# SFPGA_power.net
KiCad netlist of a schematic drawn in Altium Designer
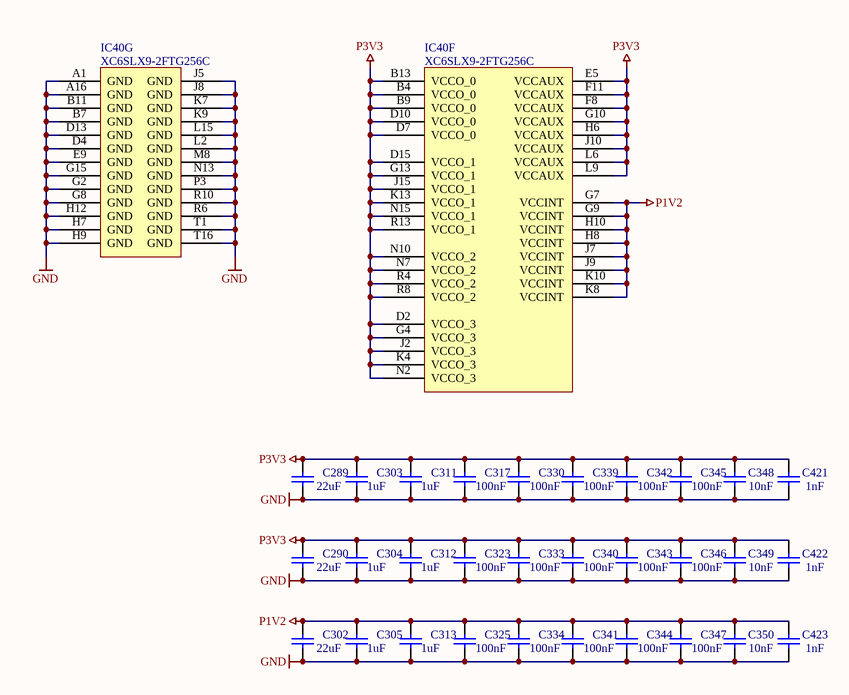
[diagram p0: SFPGA_power.SchDoc]

(export (version "E")
  (design (tool "Eeschema 10.0.6"))
  (components
    (comp (ref "C289")
      (value "22uF")
      (footprint "CAPC3216X180N")
      (description "Non-polarised capacitor")
      (fields
        (field (name "PART NUMBER") "CC1206_22UF_10V_10%_X7R")
        (field (name "VOLTAGE") "10V")
        (field (name "AUTHOR") "CERN DEM JLC")
      )
      (libsource (lib "Capacitors") (part "Capacitor - non polarized"))
    )
    (comp (ref "C290")
      (value "22uF")
      (footprint "CAPC3216X180N")
      (description "Non-polarised capacitor")
      (fields
        (field (name "PART NUMBER") "CC1206_22UF_10V_10%_X7R")
        (field (name "VOLTAGE") "10V")
        (field (name "AUTHOR") "CERN DEM JLC")
      )
      (libsource (lib "Capacitors") (part "Capacitor - non polarized"))
    )
    (comp (ref "C302")
      (value "22uF")
      (footprint "CAPC3216X180N")
      (description "Non-polarised capacitor")
      (fields
        (field (name "PART NUMBER") "CC1206_22UF_10V_10%_X7R")
        (field (name "VOLTAGE") "10V")
        (field (name "AUTHOR") "CERN DEM JLC")
      )
      (libsource (lib "Capacitors") (part "Capacitor - non polarized"))
    )
    (comp (ref "C303")
      (value "1uF")
      (footprint "CAPC1608X87N")
      (description "Non-polarised capacitor")
      (fields
        (field (name "PART NUMBER") "CC0603_1UF_16V_10%_X7R")
        (field (name "VOLTAGE") "16V")
        (field (name "AUTHOR") "CERN DEM JLC")
      )
      (libsource (lib "Capacitors") (part "Capacitor - non polarized"))
    )
    (comp (ref "C304")
      (value "1uF")
      (footprint "CAPC1608X87N")
      (description "Non-polarised capacitor")
      (fields
        (field (name "PART NUMBER") "CC0603_1UF_16V_10%_X7R")
        (field (name "VOLTAGE") "16V")
        (field (name "AUTHOR") "CERN DEM JLC")
      )
      (libsource (lib "Capacitors") (part "Capacitor - non polarized"))
    )
    (comp (ref "C305")
      (value "1uF")
      (footprint "CAPC1608X87N")
      (description "Non-polarised capacitor")
      (fields
        (field (name "PART NUMBER") "CC0603_1UF_16V_10%_X7R")
        (field (name "VOLTAGE") "16V")
        (field (name "AUTHOR") "CERN DEM JLC")
      )
      (libsource (lib "Capacitors") (part "Capacitor - non polarized"))
    )
    (comp (ref "C311")
      (value "1uF")
      (footprint "CAPC1608X87N")
      (description "Non-polarised capacitor")
      (fields
        (field (name "PART NUMBER") "CC0603_1UF_16V_10%_X7R")
        (field (name "VOLTAGE") "16V")
        (field (name "AUTHOR") "CERN DEM JLC")
      )
      (libsource (lib "Capacitors") (part "Capacitor - non polarized"))
    )
    (comp (ref "C312")
      (value "1uF")
      (footprint "CAPC1608X87N")
      (description "Non-polarised capacitor")
      (fields
        (field (name "PART NUMBER") "CC0603_1UF_16V_10%_X7R")
        (field (name "VOLTAGE") "16V")
        (field (name "AUTHOR") "CERN DEM JLC")
      )
      (libsource (lib "Capacitors") (part "Capacitor - non polarized"))
    )
    (comp (ref "C313")
      (value "1uF")
      (footprint "CAPC1608X87N")
      (description "Non-polarised capacitor")
      (fields
        (field (name "PART NUMBER") "CC0603_1UF_16V_10%_X7R")
        (field (name "VOLTAGE") "16V")
        (field (name "AUTHOR") "CERN DEM JLC")
      )
      (libsource (lib "Capacitors") (part "Capacitor - non polarized"))
    )
    (comp (ref "C317")
      (value "100nF")
      (footprint "CAPC1005X55N")
      (description "Non-polarised capacitor")
      (fields
        (field (name "PART NUMBER") "CC0402_100NF_16V_10%_X7R")
        (field (name "VOLTAGE") "16V")
        (field (name "AUTHOR") "CERN DEM JLC")
      )
      (libsource (lib "Capacitors") (part "Capacitor - non polarized"))
    )
    (comp (ref "C323")
      (value "100nF")
      (footprint "CAPC1005X55N")
      (description "Non-polarised capacitor")
      (fields
        (field (name "PART NUMBER") "CC0402_100NF_16V_10%_X7R")
        (field (name "VOLTAGE") "16V")
        (field (name "AUTHOR") "CERN DEM JLC")
      )
      (libsource (lib "Capacitors") (part "Capacitor - non polarized"))
    )
    (comp (ref "C325")
      (value "100nF")
      (footprint "CAPC1005X55N")
      (description "Non-polarised capacitor")
      (fields
        (field (name "PART NUMBER") "CC0402_100NF_16V_10%_X7R")
        (field (name "VOLTAGE") "16V")
        (field (name "AUTHOR") "CERN DEM JLC")
      )
      (libsource (lib "Capacitors") (part "Capacitor - non polarized"))
    )
    (comp (ref "C330")
      (value "100nF")
      (footprint "CAPC1005X55N")
      (description "Non-polarised capacitor")
      (fields
        (field (name "PART NUMBER") "CC0402_100NF_16V_10%_X7R")
        (field (name "VOLTAGE") "16V")
        (field (name "AUTHOR") "CERN DEM JLC")
      )
      (libsource (lib "Capacitors") (part "Capacitor - non polarized"))
    )
    (comp (ref "C333")
      (value "100nF")
      (footprint "CAPC1005X55N")
      (description "Non-polarised capacitor")
      (fields
        (field (name "PART NUMBER") "CC0402_100NF_16V_10%_X7R")
        (field (name "VOLTAGE") "16V")
        (field (name "AUTHOR") "CERN DEM JLC")
      )
      (libsource (lib "Capacitors") (part "Capacitor - non polarized"))
    )
    (comp (ref "C334")
      (value "100nF")
      (footprint "CAPC1005X55N")
      (description "Non-polarised capacitor")
      (fields
        (field (name "PART NUMBER") "CC0402_100NF_16V_10%_X7R")
        (field (name "VOLTAGE") "16V")
        (field (name "AUTHOR") "CERN DEM JLC")
      )
      (libsource (lib "Capacitors") (part "Capacitor - non polarized"))
    )
    (comp (ref "C339")
      (value "100nF")
      (footprint "CAPC1005X55N")
      (description "Non-polarised capacitor")
      (fields
        (field (name "PART NUMBER") "CC0402_100NF_16V_10%_X7R")
        (field (name "VOLTAGE") "16V")
        (field (name "AUTHOR") "CERN DEM JLC")
      )
      (libsource (lib "Capacitors") (part "Capacitor - non polarized"))
    )
    (comp (ref "C340")
      (value "100nF")
      (footprint "CAPC1005X55N")
      (description "Non-polarised capacitor")
      (fields
        (field (name "PART NUMBER") "CC0402_100NF_16V_10%_X7R")
        (field (name "VOLTAGE") "16V")
        (field (name "AUTHOR") "CERN DEM JLC")
      )
      (libsource (lib "Capacitors") (part "Capacitor - non polarized"))
    )
    (comp (ref "C341")
      (value "100nF")
      (footprint "CAPC1005X55N")
      (description "Non-polarised capacitor")
      (fields
        (field (name "PART NUMBER") "CC0402_100NF_16V_10%_X7R")
        (field (name "VOLTAGE") "16V")
        (field (name "AUTHOR") "CERN DEM JLC")
      )
      (libsource (lib "Capacitors") (part "Capacitor - non polarized"))
    )
    (comp (ref "C342")
      (value "100nF")
      (footprint "CAPC1005X55N")
      (description "Non-polarised capacitor")
      (fields
        (field (name "PART NUMBER") "CC0402_100NF_16V_10%_X7R")
        (field (name "VOLTAGE") "16V")
        (field (name "AUTHOR") "CERN DEM JLC")
      )
      (libsource (lib "Capacitors") (part "Capacitor - non polarized"))
    )
    (comp (ref "C343")
      (value "100nF")
      (footprint "CAPC1005X55N")
      (description "Non-polarised capacitor")
      (fields
        (field (name "PART NUMBER") "CC0402_100NF_16V_10%_X7R")
        (field (name "VOLTAGE") "16V")
        (field (name "AUTHOR") "CERN DEM JLC")
      )
      (libsource (lib "Capacitors") (part "Capacitor - non polarized"))
    )
    (comp (ref "C344")
      (value "100nF")
      (footprint "CAPC1005X55N")
      (description "Non-polarised capacitor")
      (fields
        (field (name "PART NUMBER") "CC0402_100NF_16V_10%_X7R")
        (field (name "VOLTAGE") "16V")
        (field (name "AUTHOR") "CERN DEM JLC")
      )
      (libsource (lib "Capacitors") (part "Capacitor - non polarized"))
    )
    (comp (ref "C345")
      (value "100nF")
      (footprint "CAPC1005X55N")
      (description "Non-polarised capacitor")
      (fields
        (field (name "PART NUMBER") "CC0402_100NF_16V_10%_X7R")
        (field (name "VOLTAGE") "16V")
        (field (name "AUTHOR") "CERN DEM JLC")
      )
      (libsource (lib "Capacitors") (part "Capacitor - non polarized"))
    )
    (comp (ref "C346")
      (value "100nF")
      (footprint "CAPC1005X55N")
      (description "Non-polarised capacitor")
      (fields
        (field (name "PART NUMBER") "CC0402_100NF_16V_10%_X7R")
        (field (name "VOLTAGE") "16V")
        (field (name "AUTHOR") "CERN DEM JLC")
      )
      (libsource (lib "Capacitors") (part "Capacitor - non polarized"))
    )
    (comp (ref "C347")
      (value "100nF")
      (footprint "CAPC1005X55N")
      (description "Non-polarised capacitor")
      (fields
        (field (name "PART NUMBER") "CC0402_100NF_16V_10%_X7R")
        (field (name "VOLTAGE") "16V")
        (field (name "AUTHOR") "CERN DEM JLC")
      )
      (libsource (lib "Capacitors") (part "Capacitor - non polarized"))
    )
    (comp (ref "C348")
      (value "10nF")
      (footprint "CAPC1608X87N")
      (description "Non-polarised capacitor")
      (fields
        (field (name "PART NUMBER") "CC0603_10NF_50V_10%_X7R")
        (field (name "VOLTAGE") "50V")
        (field (name "AUTHOR") "CERN DEM JLC")
      )
      (libsource (lib "Capacitors") (part "Capacitor - non polarized"))
    )
    (comp (ref "C349")
      (value "10nF")
      (footprint "CAPC1608X87N")
      (description "Non-polarised capacitor")
      (fields
        (field (name "PART NUMBER") "CC0603_10NF_50V_10%_X7R")
        (field (name "VOLTAGE") "50V")
        (field (name "AUTHOR") "CERN DEM JLC")
      )
      (libsource (lib "Capacitors") (part "Capacitor - non polarized"))
    )
    (comp (ref "C350")
      (value "10nF")
      (footprint "CAPC1608X87N")
      (description "Non-polarised capacitor")
      (fields
        (field (name "PART NUMBER") "CC0603_10NF_50V_10%_X7R")
        (field (name "VOLTAGE") "50V")
        (field (name "AUTHOR") "CERN DEM JLC")
      )
      (libsource (lib "Capacitors") (part "Capacitor - non polarized"))
    )
    (comp (ref "C421")
      (value "1nF")
      (footprint "CAPC1005X55N")
      (description "Non-polarised capacitor")
      (fields
        (field (name "PART NUMBER") "CC0402_1NF_50V_10%_X7R")
        (field (name "VOLTAGE") "50V")
        (field (name "AUTHOR") "CERN DEM JLC")
      )
      (libsource (lib "Capacitors") (part "Capacitor - non polarized"))
    )
    (comp (ref "C422")
      (value "1nF")
      (footprint "CAPC1005X55N")
      (description "Non-polarised capacitor")
      (fields
        (field (name "PART NUMBER") "CC0402_1NF_50V_10%_X7R")
        (field (name "VOLTAGE") "50V")
        (field (name "AUTHOR") "CERN DEM JLC")
      )
      (libsource (lib "Capacitors") (part "Capacitor - non polarized"))
    )
    (comp (ref "C423")
      (value "1nF")
      (footprint "CAPC1005X55N")
      (description "Non-polarised capacitor")
      (fields
        (field (name "PART NUMBER") "CC0402_1NF_50V_10%_X7R")
        (field (name "VOLTAGE") "50V")
        (field (name "AUTHOR") "CERN DEM JLC")
      )
      (libsource (lib "Capacitors") (part "Capacitor - non polarized"))
    )
    (comp (ref "IC40")
      (value "XC6SLX9-2FTG256C")
      (footprint "BGA256C100P16X16_1700X1700X155")
      (fields (field (name "MANUFACTURER") "XILINX") (field (name "AUTHOR") "CERN DEM JLC"))
      (libsource (lib "ICs And Semiconductors") (part "XC6SLX9-2FTG256C"))
    )
  )
  (nets
    (net (code "1") (name "GND") (class "Default")
      (node (ref "C289") (pin "1") (pinfunction "1_1") (pintype "passive"))
      (node (ref "C290") (pin "1") (pinfunction "1_1") (pintype "passive"))
      (node (ref "C302") (pin "1") (pinfunction "1_1") (pintype "passive"))
      (node (ref "C303") (pin "1") (pinfunction "1_1") (pintype "passive"))
      (node (ref "C304") (pin "1") (pinfunction "1_1") (pintype "passive"))
      (node (ref "C305") (pin "1") (pinfunction "1_1") (pintype "passive"))
      (node (ref "C311") (pin "1") (pinfunction "1_1") (pintype "passive"))
      (node (ref "C312") (pin "1") (pinfunction "1_1") (pintype "passive"))
      (node (ref "C313") (pin "1") (pinfunction "1_1") (pintype "passive"))
      (node (ref "C317") (pin "1") (pinfunction "1_1") (pintype "passive"))
      (node (ref "C323") (pin "1") (pinfunction "1_1") (pintype "passive"))
      (node (ref "C325") (pin "1") (pinfunction "1_1") (pintype "passive"))
      (node (ref "C330") (pin "1") (pinfunction "1_1") (pintype "passive"))
      (node (ref "C333") (pin "1") (pinfunction "1_1") (pintype "passive"))
      (node (ref "C334") (pin "1") (pinfunction "1_1") (pintype "passive"))
      (node (ref "C339") (pin "1") (pinfunction "1_1") (pintype "passive"))
      (node (ref "C340") (pin "1") (pinfunction "1_1") (pintype "passive"))
      (node (ref "C341") (pin "1") (pinfunction "1_1") (pintype "passive"))
      (node (ref "C342") (pin "1") (pinfunction "1_1") (pintype "passive"))
      (node (ref "C343") (pin "1") (pinfunction "1_1") (pintype "passive"))
      (node (ref "C344") (pin "1") (pinfunction "1_1") (pintype "passive"))
      (node (ref "C345") (pin "1") (pinfunction "1_1") (pintype "passive"))
      (node (ref "C346") (pin "1") (pinfunction "1_1") (pintype "passive"))
      (node (ref "C347") (pin "1") (pinfunction "1_1") (pintype "passive"))
      (node (ref "C348") (pin "1") (pinfunction "1_1") (pintype "passive"))
      (node (ref "C349") (pin "1") (pinfunction "1_1") (pintype "passive"))
      (node (ref "C350") (pin "1") (pinfunction "1_1") (pintype "passive"))
      (node (ref "C421") (pin "1") (pinfunction "1_1") (pintype "passive"))
      (node (ref "C422") (pin "1") (pinfunction "1_1") (pintype "passive"))
      (node (ref "C423") (pin "1") (pinfunction "1_1") (pintype "passive"))
      (node (ref "IC40") (pin "A1") (pinfunction "GND_A1") (pintype "power_in"))
      (node (ref "IC40") (pin "A16") (pinfunction "GND_A16") (pintype "power_in"))
      (node (ref "IC40") (pin "B11") (pinfunction "GND_B11") (pintype "power_in"))
      (node (ref "IC40") (pin "B7") (pinfunction "GND_B7") (pintype "power_in"))
      (node (ref "IC40") (pin "D13") (pinfunction "GND_D13") (pintype "power_in"))
      (node (ref "IC40") (pin "D4") (pinfunction "GND_D4") (pintype "power_in"))
      (node (ref "IC40") (pin "E9") (pinfunction "GND_E9") (pintype "power_in"))
      (node (ref "IC40") (pin "G15") (pinfunction "GND_G15") (pintype "power_in"))
      (node (ref "IC40") (pin "G2") (pinfunction "GND_G2") (pintype "power_in"))
      (node (ref "IC40") (pin "G8") (pinfunction "GND_G8") (pintype "power_in"))
      (node (ref "IC40") (pin "H12") (pinfunction "GND_H12") (pintype "power_in"))
      (node (ref "IC40") (pin "H7") (pinfunction "GND_H7") (pintype "power_in"))
      (node (ref "IC40") (pin "H9") (pinfunction "GND_H9") (pintype "power_in"))
      (node (ref "IC40") (pin "J5") (pinfunction "GND_J5") (pintype "power_in"))
      (node (ref "IC40") (pin "J8") (pinfunction "GND_J8") (pintype "power_in"))
      (node (ref "IC40") (pin "K7") (pinfunction "GND_K7") (pintype "power_in"))
      (node (ref "IC40") (pin "K9") (pinfunction "GND_K9") (pintype "power_in"))
      (node (ref "IC40") (pin "L15") (pinfunction "GND_L15") (pintype "power_in"))
      (node (ref "IC40") (pin "L2") (pinfunction "GND_L2") (pintype "power_in"))
      (node (ref "IC40") (pin "M8") (pinfunction "GND_M8") (pintype "power_in"))
      (node (ref "IC40") (pin "N13") (pinfunction "GND_N13") (pintype "power_in"))
      (node (ref "IC40") (pin "P3") (pinfunction "GND_P3") (pintype "power_in"))
      (node (ref "IC40") (pin "R10") (pinfunction "GND_R10") (pintype "power_in"))
      (node (ref "IC40") (pin "R6") (pinfunction "GND_R6") (pintype "power_in"))
      (node (ref "IC40") (pin "T1") (pinfunction "GND_T1") (pintype "power_in"))
      (node (ref "IC40") (pin "T16") (pinfunction "GND_T16") (pintype "power_in"))
    )
    (net (code "2") (name "P1V2") (class "Default")
      (node (ref "C302") (pin "2") (pinfunction "2_2") (pintype "passive"))
      (node (ref "C305") (pin "2") (pinfunction "2_2") (pintype "passive"))
      (node (ref "C313") (pin "2") (pinfunction "2_2") (pintype "passive"))
      (node (ref "C325") (pin "2") (pinfunction "2_2") (pintype "passive"))
      (node (ref "C334") (pin "2") (pinfunction "2_2") (pintype "passive"))
      (node (ref "C341") (pin "2") (pinfunction "2_2") (pintype "passive"))
      (node (ref "C344") (pin "2") (pinfunction "2_2") (pintype "passive"))
      (node (ref "C347") (pin "2") (pinfunction "2_2") (pintype "passive"))
      (node (ref "C350") (pin "2") (pinfunction "2_2") (pintype "passive"))
      (node (ref "C423") (pin "2") (pinfunction "2_2") (pintype "passive"))
      (node (ref "IC40") (pin "G7") (pinfunction "VCCINT_G7") (pintype "power_in"))
      (node (ref "IC40") (pin "G9") (pinfunction "VCCINT_G9") (pintype "power_in"))
      (node (ref "IC40") (pin "H10") (pinfunction "VCCINT_H10") (pintype "power_in"))
      (node (ref "IC40") (pin "H8") (pinfunction "VCCINT_H8") (pintype "power_in"))
      (node (ref "IC40") (pin "J7") (pinfunction "VCCINT_J7") (pintype "power_in"))
      (node (ref "IC40") (pin "J9") (pinfunction "VCCINT_J9") (pintype "power_in"))
      (node (ref "IC40") (pin "K10") (pinfunction "VCCINT_K10") (pintype "power_in"))
      (node (ref "IC40") (pin "K8") (pinfunction "VCCINT_K8") (pintype "power_in"))
    )
    (net (code "3") (name "P3V3") (class "Default")
      (node (ref "C289") (pin "2") (pinfunction "2_2") (pintype "passive"))
      (node (ref "C290") (pin "2") (pinfunction "2_2") (pintype "passive"))
      (node (ref "C303") (pin "2") (pinfunction "2_2") (pintype "passive"))
      (node (ref "C304") (pin "2") (pinfunction "2_2") (pintype "passive"))
      (node (ref "C311") (pin "2") (pinfunction "2_2") (pintype "passive"))
      (node (ref "C312") (pin "2") (pinfunction "2_2") (pintype "passive"))
      (node (ref "C317") (pin "2") (pinfunction "2_2") (pintype "passive"))
      (node (ref "C323") (pin "2") (pinfunction "2_2") (pintype "passive"))
      (node (ref "C330") (pin "2") (pinfunction "2_2") (pintype "passive"))
      (node (ref "C333") (pin "2") (pinfunction "2_2") (pintype "passive"))
      (node (ref "C339") (pin "2") (pinfunction "2_2") (pintype "passive"))
      (node (ref "C340") (pin "2") (pinfunction "2_2") (pintype "passive"))
      (node (ref "C342") (pin "2") (pinfunction "2_2") (pintype "passive"))
      (node (ref "C343") (pin "2") (pinfunction "2_2") (pintype "passive"))
      (node (ref "C345") (pin "2") (pinfunction "2_2") (pintype "passive"))
      (node (ref "C346") (pin "2") (pinfunction "2_2") (pintype "passive"))
      (node (ref "C348") (pin "2") (pinfunction "2_2") (pintype "passive"))
      (node (ref "C349") (pin "2") (pinfunction "2_2") (pintype "passive"))
      (node (ref "C421") (pin "2") (pinfunction "2_2") (pintype "passive"))
      (node (ref "C422") (pin "2") (pinfunction "2_2") (pintype "passive"))
      (node (ref "IC40") (pin "B13") (pinfunction "VCCO_0_B13") (pintype "power_in"))
      (node (ref "IC40") (pin "B4") (pinfunction "VCCO_0_B4") (pintype "power_in"))
      (node (ref "IC40") (pin "B9") (pinfunction "VCCO_0_B9") (pintype "power_in"))
      (node (ref "IC40") (pin "D10") (pinfunction "VCCO_0_D10") (pintype "power_in"))
      (node (ref "IC40") (pin "D15") (pinfunction "VCCO_1_D15") (pintype "power_in"))
      (node (ref "IC40") (pin "D2") (pinfunction "VCCO_3_D2") (pintype "power_in"))
      (node (ref "IC40") (pin "D7") (pinfunction "VCCO_0_D7") (pintype "power_in"))
      (node (ref "IC40") (pin "E5") (pinfunction "VCCAUX_E5") (pintype "power_in"))
      (node (ref "IC40") (pin "F11") (pinfunction "VCCAUX_F11") (pintype "power_in"))
      (node (ref "IC40") (pin "F8") (pinfunction "VCCAUX_F8") (pintype "power_in"))
      (node (ref "IC40") (pin "G10") (pinfunction "VCCAUX_G10") (pintype "power_in"))
      (node (ref "IC40") (pin "G13") (pinfunction "VCCO_1_G13") (pintype "power_in"))
      (node (ref "IC40") (pin "G4") (pinfunction "VCCO_3_G4") (pintype "power_in"))
      (node (ref "IC40") (pin "H6") (pinfunction "VCCAUX_H6") (pintype "power_in"))
      (node (ref "IC40") (pin "J10") (pinfunction "VCCAUX_J10") (pintype "power_in"))
      (node (ref "IC40") (pin "J15") (pinfunction "VCCO_1_J15") (pintype "power_in"))
      (node (ref "IC40") (pin "J2") (pinfunction "VCCO_3_J2") (pintype "power_in"))
      (node (ref "IC40") (pin "K13") (pinfunction "VCCO_1_K13") (pintype "power_in"))
      (node (ref "IC40") (pin "K4") (pinfunction "VCCO_3_K4") (pintype "power_in"))
      (node (ref "IC40") (pin "L6") (pinfunction "VCCAUX_L6") (pintype "power_in"))
      (node (ref "IC40") (pin "L9") (pinfunction "VCCAUX_L9") (pintype "power_in"))
      (node (ref "IC40") (pin "N10") (pinfunction "VCCO_2_N10") (pintype "power_in"))
      (node (ref "IC40") (pin "N15") (pinfunction "VCCO_1_N15") (pintype "power_in"))
      (node (ref "IC40") (pin "N2") (pinfunction "VCCO_3_N2") (pintype "power_in"))
      (node (ref "IC40") (pin "N7") (pinfunction "VCCO_2_N7") (pintype "power_in"))
      (node (ref "IC40") (pin "R13") (pinfunction "VCCO_1_R13") (pintype "power_in"))
      (node (ref "IC40") (pin "R4") (pinfunction "VCCO_2_R4") (pintype "power_in"))
      (node (ref "IC40") (pin "R8") (pinfunction "VCCO_2_R8") (pintype "power_in"))
    )
  )
)
